# Sheet.net
KiCad netlist of a schematic drawn in Altium Designer
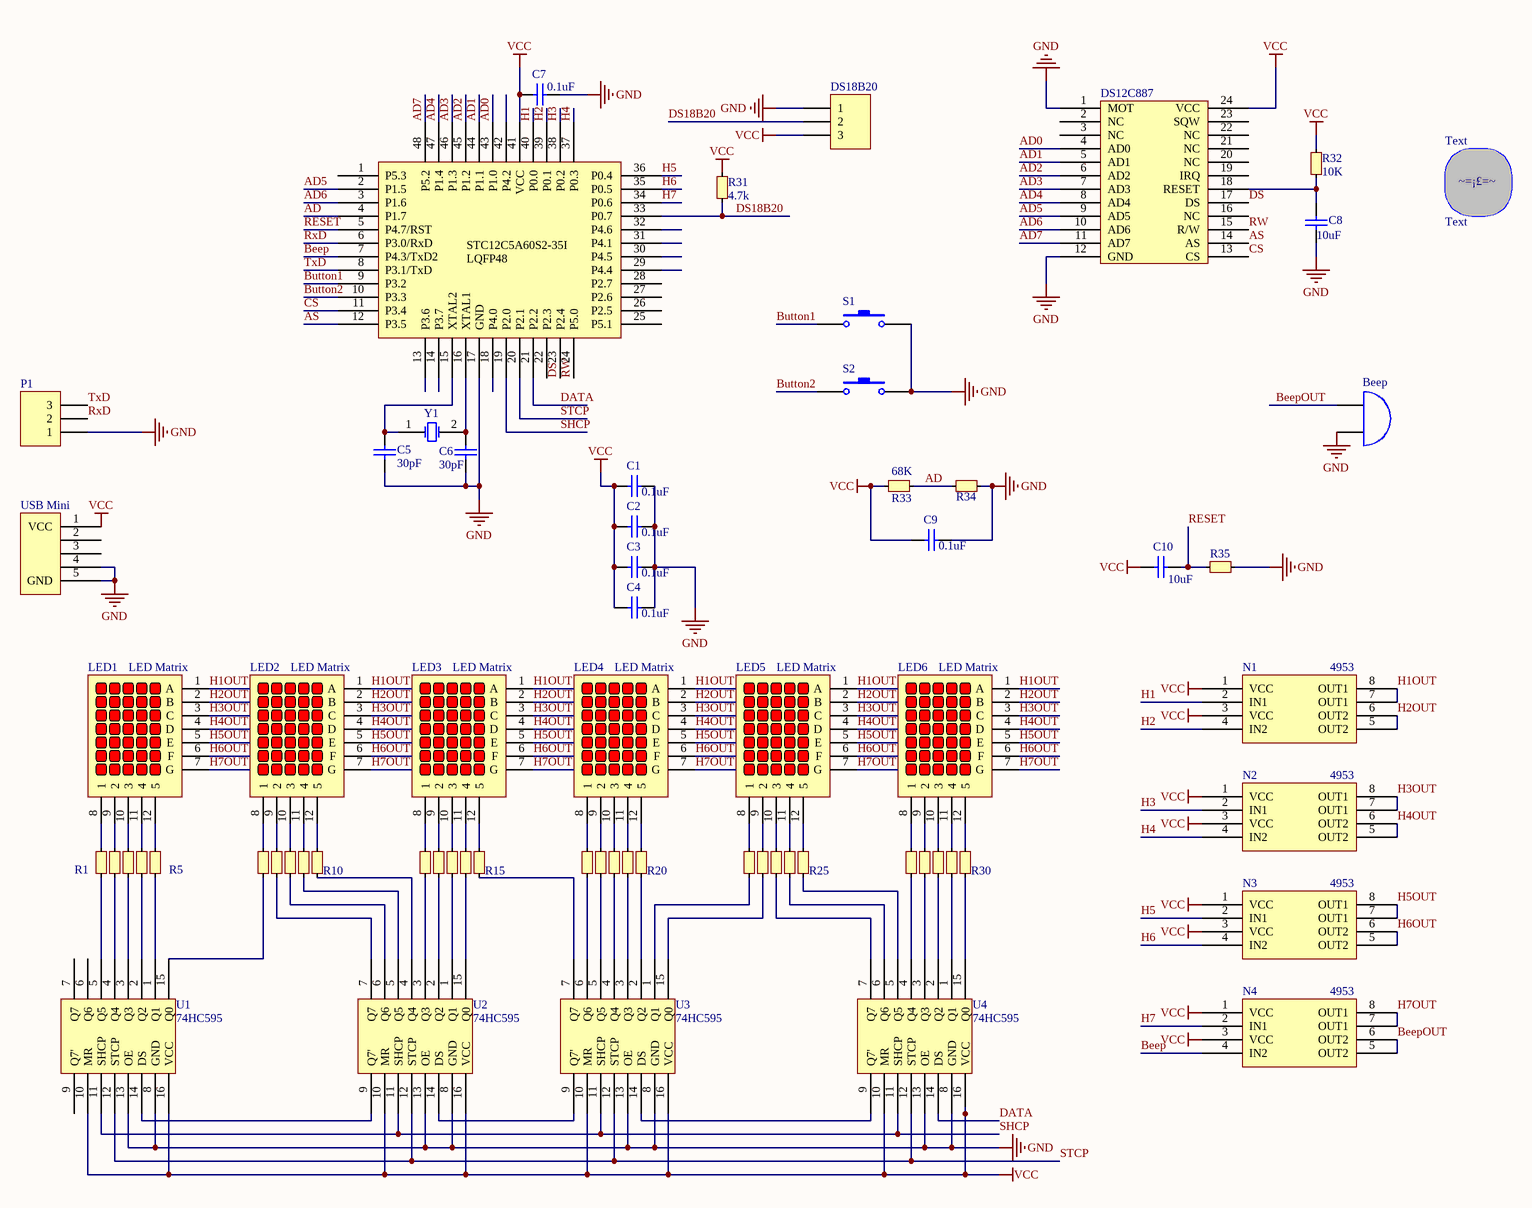
[diagram p0: Sheet.SchDoc]

(export (version "E")
  (design (tool "Eeschema 10.0.6"))
  (components
    (comp (ref "Beep")
      (value "Bell")
      (footprint "Beep")
      (description "Electrical Bell")
      (fields (field (name "PUBLISHER") "Altium Limited"))
      (libsource (lib "Miscellaneous Devices") (part "Bell"))
    )
    (comp (ref "C1")
      (value "0.1uF")
      (footprint "0805 - duplicate")
      (description "Capacitor")
      (fields (field (name "Comment") "Cap") (field (name "PUBLISHER") "Altium Limited"))
      (libsource (lib "Miscellaneous Devices") (part "Cap"))
    )
    (comp (ref "C2")
      (value "0.1uF")
      (footprint "0805 - duplicate")
      (description "Capacitor")
      (fields (field (name "Comment") "Cap") (field (name "PUBLISHER") "Altium Limited"))
      (libsource (lib "Miscellaneous Devices") (part "Cap"))
    )
    (comp (ref "C3")
      (value "0.1uF")
      (footprint "0805 - duplicate")
      (description "Capacitor")
      (fields (field (name "Comment") "Cap") (field (name "PUBLISHER") "Altium Limited"))
      (libsource (lib "Miscellaneous Devices") (part "Cap"))
    )
    (comp (ref "C4")
      (value "0.1uF")
      (footprint "0805 - duplicate")
      (description "Capacitor")
      (fields (field (name "Comment") "Cap") (field (name "PUBLISHER") "Altium Limited"))
      (libsource (lib "Miscellaneous Devices") (part "Cap"))
    )
    (comp (ref "C5")
      (value "30pF")
      (footprint "0805 - duplicate")
      (description "Capacitor")
      (fields (field (name "Comment") "Cap") (field (name "PUBLISHER") "Altium Limited"))
      (libsource (lib "Miscellaneous Devices") (part "Cap"))
    )
    (comp (ref "C6")
      (value "30pF")
      (footprint "0805 - duplicate")
      (description "Capacitor")
      (fields (field (name "Comment") "Cap") (field (name "PUBLISHER") "Altium Limited"))
      (libsource (lib "Miscellaneous Devices") (part "Cap"))
    )
    (comp (ref "C7")
      (value "0.1uF")
      (footprint "0805 - duplicate")
      (description "Capacitor")
      (fields (field (name "Comment") "Cap") (field (name "PUBLISHER") "Altium Limited"))
      (libsource (lib "Miscellaneous Devices") (part "Cap"))
    )
    (comp (ref "C8")
      (value "10uF")
      (footprint "0805 - duplicate")
      (description "Capacitor")
      (fields (field (name "Comment") "Cap") (field (name "PUBLISHER") "Altium Limited"))
      (libsource (lib "Miscellaneous Devices") (part "Cap"))
    )
    (comp (ref "C9")
      (value "0.1uF")
      (footprint "0805 - duplicate")
      (description "Capacitor")
      (fields (field (name "Comment") "Cap") (field (name "PUBLISHER") "Altium Limited"))
      (libsource (lib "Miscellaneous Devices") (part "Cap"))
    )
    (comp (ref "C10")
      (value "10uF")
      (footprint "0805 - duplicate")
      (description "Capacitor")
      (fields (field (name "Comment") "Cap") (field (name "PUBLISHER") "Altium Limited"))
      (libsource (lib "Miscellaneous Devices") (part "Cap"))
    )
    (comp (ref "DS12C887")
      (value "DS12C887")
      (footprint "Timer")
      (libsource (lib "Schlib") (part "DS12C887"))
    )
    (comp (ref "DS18B20")
      (value "Header 3")
      (footprint "TO-92")
      (description "Header, 3-Pin")
      (fields (field (name "PUBLISHER") "Altium Limited"))
      (libsource (lib "Miscellaneous Connectors") (part "Header 3"))
    )
    (comp (ref "LED1")
      (value "LED Matrix")
      (footprint "LED-Matrix 5*7")
      (fields (field (name "PUBLISHER") "Altium Limited"))
      (libsource (lib "Schlib") (part "LED-Matrix 5*7"))
    )
    (comp (ref "LED2")
      (value "LED Matrix")
      (footprint "LED-Matrix 5*7")
      (fields (field (name "PUBLISHER") "Altium Limited"))
      (libsource (lib "Schlib") (part "LED-Matrix 5*7"))
    )
    (comp (ref "LED3")
      (value "LED Matrix")
      (footprint "LED-Matrix 5*7")
      (fields (field (name "PUBLISHER") "Altium Limited"))
      (libsource (lib "Schlib") (part "LED-Matrix 5*7"))
    )
    (comp (ref "LED4")
      (value "LED Matrix")
      (footprint "LED-Matrix 5*7")
      (fields (field (name "PUBLISHER") "Altium Limited"))
      (libsource (lib "Schlib") (part "LED-Matrix 5*7"))
    )
    (comp (ref "LED5")
      (value "LED Matrix")
      (footprint "LED-Matrix 5*7")
      (fields (field (name "PUBLISHER") "Altium Limited"))
      (libsource (lib "Schlib") (part "LED-Matrix 5*7"))
    )
    (comp (ref "LED6")
      (value "LED Matrix")
      (footprint "LED-Matrix 5*7")
      (fields (field (name "PUBLISHER") "Altium Limited"))
      (libsource (lib "Schlib") (part "LED-Matrix 5*7"))
    )
    (comp (ref "MCU")
      (value "STC12C5A60S2-35I-LQFP48")
      (footprint "MCU")
      (libsource (lib "Schlib") (part "STC12C5A60S2-35I-LQFP48"))
    )
    (comp (ref "N1") (value "4953") (footprint "SO8_L") (libsource (lib "Schlib") (part "4953")))
    (comp (ref "N2") (value "4953") (footprint "SO8_L") (libsource (lib "Schlib") (part "4953")))
    (comp (ref "N3") (value "4953") (footprint "SO8_L") (libsource (lib "Schlib") (part "4953")))
    (comp (ref "N4") (value "4953") (footprint "SO8_L") (libsource (lib "Schlib") (part "4953")))
    (comp (ref "P1")
      (value "Header 3")
      (footprint "HDR1X3")
      (description "Header, 3-Pin")
      (fields (field (name "PUBLISHER") "Altium Limited"))
      (libsource (lib "") (part "Header 3_1"))
    )
    (comp (ref "R1") (value "Res") (footprint "0805") (libsource (lib "Schlib") (part "Res")))
    (comp (ref "R2") (value "Res") (footprint "0805") (libsource (lib "Schlib") (part "Res")))
    (comp (ref "R3") (value "Res") (footprint "0805") (libsource (lib "Schlib") (part "Res")))
    (comp (ref "R4") (value "Res") (footprint "0805") (libsource (lib "Schlib") (part "Res")))
    (comp (ref "R5") (value "Res") (footprint "0805") (libsource (lib "Schlib") (part "Res")))
    (comp (ref "R6") (value "Res") (footprint "0805") (libsource (lib "Schlib") (part "Res")))
    (comp (ref "R7") (value "Res") (footprint "0805") (libsource (lib "Schlib") (part "Res")))
    (comp (ref "R8") (value "Res") (footprint "0805") (libsource (lib "Schlib") (part "Res")))
    (comp (ref "R9") (value "Res") (footprint "0805") (libsource (lib "Schlib") (part "Res")))
    (comp (ref "R10") (value "Res") (footprint "0805") (libsource (lib "Schlib") (part "Res")))
    (comp (ref "R11") (value "Res") (footprint "0805") (libsource (lib "Schlib") (part "Res")))
    (comp (ref "R12") (value "Res") (footprint "0805") (libsource (lib "Schlib") (part "Res")))
    (comp (ref "R13") (value "Res") (footprint "0805") (libsource (lib "Schlib") (part "Res")))
    (comp (ref "R14") (value "Res") (footprint "0805") (libsource (lib "Schlib") (part "Res")))
    (comp (ref "R15") (value "Res") (footprint "0805") (libsource (lib "Schlib") (part "Res")))
    (comp (ref "R16") (value "Res") (footprint "0805") (libsource (lib "Schlib") (part "Res")))
    (comp (ref "R17") (value "Res") (footprint "0805") (libsource (lib "Schlib") (part "Res")))
    (comp (ref "R18") (value "Res") (footprint "0805") (libsource (lib "Schlib") (part "Res")))
    (comp (ref "R19") (value "Res") (footprint "0805") (libsource (lib "Schlib") (part "Res")))
    (comp (ref "R20") (value "Res") (footprint "0805") (libsource (lib "Schlib") (part "Res")))
    (comp (ref "R21") (value "Res") (footprint "0805") (libsource (lib "Schlib") (part "Res")))
    (comp (ref "R22") (value "Res") (footprint "0805") (libsource (lib "Schlib") (part "Res")))
    (comp (ref "R23") (value "Res") (footprint "0805") (libsource (lib "Schlib") (part "Res")))
    (comp (ref "R24") (value "Res") (footprint "0805") (libsource (lib "Schlib") (part "Res")))
    (comp (ref "R25") (value "Res") (footprint "0805") (libsource (lib "Schlib") (part "Res")))
    (comp (ref "R26") (value "Res") (footprint "0805") (libsource (lib "Schlib") (part "Res")))
    (comp (ref "R27") (value "Res") (footprint "0805") (libsource (lib "Schlib") (part "Res")))
    (comp (ref "R28") (value "Res") (footprint "0805") (libsource (lib "Schlib") (part "Res")))
    (comp (ref "R29") (value "Res") (footprint "0805") (libsource (lib "Schlib") (part "Res")))
    (comp (ref "R30") (value "Res") (footprint "0805") (libsource (lib "Schlib") (part "Res")))
    (comp (ref "R31") (value "4.7k") (footprint "0805") (libsource (lib "Schlib") (part "Res")))
    (comp (ref "R32") (value "10K") (footprint "0805") (libsource (lib "Schlib") (part "Res")))
    (comp (ref "R33") (value "68K") (footprint "0805") (libsource (lib "") (part "Res_1")))
    (comp (ref "R34") (value "Res") (footprint "R38") (libsource (lib "") (part "Res_1")))
    (comp (ref "R35") (value "Res") (footprint "0805") (libsource (lib "") (part "Res_1")))
    (comp (ref "S1")
      (value "SW-PB")
      (footprint "Button")
      (description "Switch")
      (fields (field (name "PUBLISHER") "Altium Limited"))
      (libsource (lib "Miscellaneous Devices") (part "SW-PB"))
    )
    (comp (ref "S2")
      (value "SW-PB")
      (footprint "Button")
      (description "Switch")
      (fields (field (name "PUBLISHER") "Altium Limited"))
      (libsource (lib "Miscellaneous Devices") (part "SW-PB"))
    )
    (comp (ref "Text") (value "Text") (footprint "TUSIJI_8") (libsource (lib "Schlib") (part "Text")))
    (comp (ref "U1") (value "74HC595") (footprint "SO-16_L") (libsource (lib "Schlib") (part "74HC595")))
    (comp (ref "U2") (value "74HC595") (footprint "SO-16_L") (libsource (lib "Schlib") (part "74HC595")))
    (comp (ref "U3") (value "74HC595") (footprint "SO-16_L") (libsource (lib "Schlib") (part "74HC595")))
    (comp (ref "U4") (value "74HC595") (footprint "SO-16_L") (libsource (lib "Schlib") (part "74HC595")))
    (comp (ref "USB Mini") (value "~") (footprint "Micro_USB") (libsource (lib "Schlib") (part "USB")))
    (comp (ref "Y1")
      (value "XTAL")
      (footprint "5023")
      (description "Crystal Oscillator")
      (fields (field (name "PUBLISHER") "Altium Limited"))
      (libsource (lib "Miscellaneous Devices") (part "XTAL"))
    )
  )
  (nets
    (net (code "1") (name "/AD") (class "Default")
      (node (ref "MCU") (pin "4") (pinfunction "P1.7_4") (pintype "passive"))
      (node (ref "R33") (pin "1") (pintype "passive"))
      (node (ref "R34") (pin "0") (pintype "passive"))
    )
    (net (code "2") (name "/AD0") (class "Default")
      (node (ref "DS12C887") (pin "4") (pinfunction "AD0_4") (pintype "passive"))
      (node (ref "MCU") (pin "43") (pinfunction "P1.0_43") (pintype "passive"))
    )
    (net (code "3") (name "/AD1") (class "Default")
      (node (ref "DS12C887") (pin "5") (pinfunction "AD1_5") (pintype "passive"))
      (node (ref "MCU") (pin "44") (pinfunction "P1.1_44") (pintype "passive"))
    )
    (net (code "4") (name "/AD2") (class "Default")
      (node (ref "DS12C887") (pin "6") (pinfunction "AD2_6") (pintype "passive"))
      (node (ref "MCU") (pin "45") (pinfunction "P1.2_45") (pintype "passive"))
    )
    (net (code "5") (name "/AD3") (class "Default")
      (node (ref "DS12C887") (pin "7") (pinfunction "AD3_7") (pintype "passive"))
      (node (ref "MCU") (pin "46") (pinfunction "P1.3_46") (pintype "passive"))
    )
    (net (code "6") (name "/AD4") (class "Default")
      (node (ref "DS12C887") (pin "8") (pinfunction "AD4_8") (pintype "passive"))
      (node (ref "MCU") (pin "47") (pinfunction "P1.4_47") (pintype "passive"))
    )
    (net (code "7") (name "/AD5") (class "Default")
      (node (ref "DS12C887") (pin "9") (pinfunction "AD5_9") (pintype "passive"))
      (node (ref "MCU") (pin "2") (pinfunction "P1.5_2") (pintype "passive"))
    )
    (net (code "8") (name "/AD6") (class "Default")
      (node (ref "DS12C887") (pin "10") (pinfunction "AD6_10") (pintype "passive"))
      (node (ref "MCU") (pin "3") (pinfunction "P1.6_3") (pintype "passive"))
    )
    (net (code "9") (name "/AD7") (class "Default")
      (node (ref "DS12C887") (pin "11") (pinfunction "AD7_11") (pintype "passive"))
      (node (ref "MCU") (pin "48") (pinfunction "P5.2_48") (pintype "passive"))
    )
    (net (code "10") (name "/AS") (class "Default")
      (node (ref "DS12C887") (pin "14") (pinfunction "AS_14") (pintype "passive"))
      (node (ref "MCU") (pin "12") (pinfunction "P3.5_12") (pintype "passive"))
    )
    (net (code "11") (name "/Beep") (class "Default")
      (node (ref "MCU") (pin "7") (pinfunction "P4.3/TxD2_7") (pintype "passive"))
      (node (ref "N4") (pin "4") (pinfunction "IN2_4") (pintype "passive"))
    )
    (net (code "12") (name "/BeepOUT") (class "Default")
      (node (ref "Beep") (pin "1") (pinfunction "A_1") (pintype "passive"))
      (node (ref "N4") (pin "5") (pinfunction "OUT2_5") (pintype "passive"))
      (node (ref "N4") (pin "6") (pinfunction "OUT2_6") (pintype "passive"))
    )
    (net (code "13") (name "/Button1") (class "Default")
      (node (ref "MCU") (pin "9") (pinfunction "P3.2_9") (pintype "passive"))
      (node (ref "S1") (pin "1") (pinfunction "1_1") (pintype "passive"))
    )
    (net (code "14") (name "/Button2") (class "Default")
      (node (ref "MCU") (pin "10") (pinfunction "P3.3_10") (pintype "passive"))
      (node (ref "S2") (pin "1") (pinfunction "1_1") (pintype "passive"))
    )
    (net (code "15") (name "/CS") (class "Default")
      (node (ref "DS12C887") (pin "13") (pinfunction "CS_13") (pintype "passive"))
      (node (ref "MCU") (pin "11") (pinfunction "P3.4_11") (pintype "passive"))
    )
    (net (code "16") (name "/DATA") (class "Default")
      (node (ref "MCU") (pin "21") (pinfunction "P2.2_21") (pintype "passive"))
      (node (ref "U4") (pin "14") (pinfunction "DS_14") (pintype "passive"))
    )
    (net (code "17") (name "/DS") (class "Default")
      (node (ref "DS12C887") (pin "17") (pinfunction "DS_17") (pintype "passive"))
      (node (ref "MCU") (pin "23") (pinfunction "P2.4_23") (pintype "passive"))
    )
    (net (code "18") (name "/DS18B20") (class "Default")
      (node (ref "DS18B20") (pin "2") (pinfunction "2_2") (pintype "passive"))
      (node (ref "MCU") (pin "33") (pinfunction "P0.7_33") (pintype "passive"))
      (node (ref "R31") (pin "0") (pintype "passive"))
    )
    (net (code "19") (name "/H1") (class "Default")
      (node (ref "MCU") (pin "40") (pinfunction "P0.0_40") (pintype "passive"))
      (node (ref "N1") (pin "2") (pinfunction "IN1_2") (pintype "passive"))
    )
    (net (code "20") (name "/H1OUT") (class "Default")
      (node (ref "LED1") (pin "1") (pinfunction "A_1") (pintype "passive"))
      (node (ref "LED2") (pin "1") (pinfunction "A_1") (pintype "passive"))
      (node (ref "LED3") (pin "1") (pinfunction "A_1") (pintype "passive"))
      (node (ref "LED4") (pin "1") (pinfunction "A_1") (pintype "passive"))
      (node (ref "LED5") (pin "1") (pinfunction "A_1") (pintype "passive"))
      (node (ref "LED6") (pin "1") (pinfunction "A_1") (pintype "passive"))
      (node (ref "N1") (pin "7") (pinfunction "OUT1_7") (pintype "passive"))
      (node (ref "N1") (pin "8") (pinfunction "OUT1_8") (pintype "passive"))
    )
    (net (code "21") (name "/H2") (class "Default")
      (node (ref "MCU") (pin "39") (pinfunction "P0.1_39") (pintype "passive"))
      (node (ref "N1") (pin "4") (pinfunction "IN2_4") (pintype "passive"))
    )
    (net (code "22") (name "/H2OUT") (class "Default")
      (node (ref "LED1") (pin "2") (pinfunction "B_2") (pintype "passive"))
      (node (ref "LED2") (pin "2") (pinfunction "B_2") (pintype "passive"))
      (node (ref "LED3") (pin "2") (pinfunction "B_2") (pintype "passive"))
      (node (ref "LED4") (pin "2") (pinfunction "B_2") (pintype "passive"))
      (node (ref "LED5") (pin "2") (pinfunction "B_2") (pintype "passive"))
      (node (ref "LED6") (pin "2") (pinfunction "B_2") (pintype "passive"))
      (node (ref "N1") (pin "5") (pinfunction "OUT2_5") (pintype "passive"))
      (node (ref "N1") (pin "6") (pinfunction "OUT2_6") (pintype "passive"))
    )
    (net (code "23") (name "/H3") (class "Default")
      (node (ref "MCU") (pin "38") (pinfunction "P0.2_38") (pintype "passive"))
      (node (ref "N2") (pin "2") (pinfunction "IN1_2") (pintype "passive"))
    )
    (net (code "24") (name "/H3OUT") (class "Default")
      (node (ref "LED1") (pin "3") (pinfunction "C_3") (pintype "passive"))
      (node (ref "LED2") (pin "3") (pinfunction "C_3") (pintype "passive"))
      (node (ref "LED3") (pin "3") (pinfunction "C_3") (pintype "passive"))
      (node (ref "LED4") (pin "3") (pinfunction "C_3") (pintype "passive"))
      (node (ref "LED5") (pin "3") (pinfunction "C_3") (pintype "passive"))
      (node (ref "LED6") (pin "3") (pinfunction "C_3") (pintype "passive"))
      (node (ref "N2") (pin "7") (pinfunction "OUT1_7") (pintype "passive"))
      (node (ref "N2") (pin "8") (pinfunction "OUT1_8") (pintype "passive"))
    )
    (net (code "25") (name "/H4") (class "Default")
      (node (ref "MCU") (pin "37") (pinfunction "P0.3_37") (pintype "passive"))
      (node (ref "N2") (pin "4") (pinfunction "IN2_4") (pintype "passive"))
    )
    (net (code "26") (name "/H4OUT") (class "Default")
      (node (ref "LED1") (pin "4") (pinfunction "D_4") (pintype "passive"))
      (node (ref "LED2") (pin "4") (pinfunction "D_4") (pintype "passive"))
      (node (ref "LED3") (pin "4") (pinfunction "D_4") (pintype "passive"))
      (node (ref "LED4") (pin "4") (pinfunction "D_4") (pintype "passive"))
      (node (ref "LED5") (pin "4") (pinfunction "D_4") (pintype "passive"))
      (node (ref "LED6") (pin "4") (pinfunction "D_4") (pintype "passive"))
      (node (ref "N2") (pin "5") (pinfunction "OUT2_5") (pintype "passive"))
      (node (ref "N2") (pin "6") (pinfunction "OUT2_6") (pintype "passive"))
    )
    (net (code "27") (name "/H5") (class "Default")
      (node (ref "MCU") (pin "36") (pinfunction "P0.4_36") (pintype "passive"))
      (node (ref "N3") (pin "2") (pinfunction "IN1_2") (pintype "passive"))
    )
    (net (code "28") (name "/H5OUT") (class "Default")
      (node (ref "LED1") (pin "5") (pinfunction "E_5") (pintype "passive"))
      (node (ref "LED2") (pin "5") (pinfunction "E_5") (pintype "passive"))
      (node (ref "LED3") (pin "5") (pinfunction "E_5") (pintype "passive"))
      (node (ref "LED4") (pin "5") (pinfunction "E_5") (pintype "passive"))
      (node (ref "LED5") (pin "5") (pinfunction "E_5") (pintype "passive"))
      (node (ref "LED6") (pin "5") (pinfunction "E_5") (pintype "passive"))
      (node (ref "N3") (pin "7") (pinfunction "OUT1_7") (pintype "passive"))
      (node (ref "N3") (pin "8") (pinfunction "OUT1_8") (pintype "passive"))
    )
    (net (code "29") (name "/H6") (class "Default")
      (node (ref "MCU") (pin "35") (pinfunction "P0.5_35") (pintype "passive"))
      (node (ref "N3") (pin "4") (pinfunction "IN2_4") (pintype "passive"))
    )
    (net (code "30") (name "/H6OUT") (class "Default")
      (node (ref "LED1") (pin "6") (pinfunction "F_6") (pintype "passive"))
      (node (ref "LED2") (pin "6") (pinfunction "F_6") (pintype "passive"))
      (node (ref "LED3") (pin "6") (pinfunction "F_6") (pintype "passive"))
      (node (ref "LED4") (pin "6") (pinfunction "F_6") (pintype "passive"))
      (node (ref "LED5") (pin "6") (pinfunction "F_6") (pintype "passive"))
      (node (ref "LED6") (pin "6") (pinfunction "F_6") (pintype "passive"))
      (node (ref "N3") (pin "5") (pinfunction "OUT2_5") (pintype "passive"))
      (node (ref "N3") (pin "6") (pinfunction "OUT2_6") (pintype "passive"))
    )
    (net (code "31") (name "/H7") (class "Default")
      (node (ref "MCU") (pin "34") (pinfunction "P0.6_34") (pintype "passive"))
      (node (ref "N4") (pin "2") (pinfunction "IN1_2") (pintype "passive"))
    )
    (net (code "32") (name "/H7OUT") (class "Default")
      (node (ref "LED1") (pin "7") (pinfunction "G_7") (pintype "passive"))
      (node (ref "LED2") (pin "7") (pinfunction "G_7") (pintype "passive"))
      (node (ref "LED3") (pin "7") (pinfunction "G_7") (pintype "passive"))
      (node (ref "LED4") (pin "7") (pinfunction "G_7") (pintype "passive"))
      (node (ref "LED5") (pin "7") (pinfunction "G_7") (pintype "passive"))
      (node (ref "LED6") (pin "7") (pinfunction "G_7") (pintype "passive"))
      (node (ref "N4") (pin "7") (pinfunction "OUT1_7") (pintype "passive"))
      (node (ref "N4") (pin "8") (pinfunction "OUT1_8") (pintype "passive"))
    )
    (net (code "33") (name "/RESET") (class "Default")
      (node (ref "C10") (pin "2") (pinfunction "2_2") (pintype "passive"))
      (node (ref "MCU") (pin "5") (pinfunction "P4.7/RST_5") (pintype "passive"))
      (node (ref "R35") (pin "0") (pintype "passive"))
    )
    (net (code "34") (name "/RW") (class "Default")
      (node (ref "DS12C887") (pin "15") (pinfunction "R/W_15") (pintype "passive"))
      (node (ref "MCU") (pin "24") (pinfunction "P5.0_24") (pintype "passive"))
    )
    (net (code "35") (name "/RxD") (class "Default")
      (node (ref "MCU") (pin "6") (pinfunction "P3.0/RxD_6") (pintype "passive"))
      (node (ref "P1") (pin "2") (pinfunction "2_2") (pintype "passive"))
    )
    (net (code "36") (name "/SHCP") (class "Default")
      (node (ref "MCU") (pin "19") (pinfunction "P2.0_19") (pintype "passive"))
      (node (ref "U1") (pin "11") (pinfunction "SHCP_11") (pintype "passive"))
      (node (ref "U2") (pin "11") (pinfunction "SHCP_11") (pintype "passive"))
      (node (ref "U3") (pin "11") (pinfunction "SHCP_11") (pintype "passive"))
      (node (ref "U4") (pin "11") (pinfunction "SHCP_11") (pintype "passive"))
    )
    (net (code "37") (name "/STCP") (class "Default")
      (node (ref "MCU") (pin "20") (pinfunction "P2.1_20") (pintype "passive"))
      (node (ref "U1") (pin "12") (pinfunction "STCP_12") (pintype "passive"))
      (node (ref "U2") (pin "12") (pinfunction "STCP_12") (pintype "passive"))
      (node (ref "U3") (pin "12") (pinfunction "STCP_12") (pintype "passive"))
      (node (ref "U4") (pin "12") (pinfunction "STCP_12") (pintype "passive"))
    )
    (net (code "38") (name "/TxD") (class "Default")
      (node (ref "MCU") (pin "8") (pinfunction "P3.1/TxD_8") (pintype "passive"))
      (node (ref "P1") (pin "3") (pinfunction "3_3") (pintype "passive"))
    )
    (net (code "39") (name "GND") (class "Default")
      (node (ref "Beep") (pin "2") (pinfunction "B_2") (pintype "passive"))
      (node (ref "C1") (pin "2") (pinfunction "2_2") (pintype "passive"))
      (node (ref "C2") (pin "2") (pinfunction "2_2") (pintype "passive"))
      (node (ref "C3") (pin "2") (pinfunction "2_2") (pintype "passive"))
      (node (ref "C4") (pin "2") (pinfunction "2_2") (pintype "passive"))
      (node (ref "C5") (pin "1") (pinfunction "1_1") (pintype "passive"))
      (node (ref "C6") (pin "1") (pinfunction "1_1") (pintype "passive"))
      (node (ref "C7") (pin "2") (pinfunction "2_2") (pintype "passive"))
      (node (ref "C8") (pin "1") (pinfunction "1_1") (pintype "passive"))
      (node (ref "C9") (pin "2") (pinfunction "2_2") (pintype "passive"))
      (node (ref "DS12C887") (pin "1") (pinfunction "MOT_1") (pintype "passive"))
      (node (ref "DS12C887") (pin "12") (pinfunction "GND_12") (pintype "passive"))
      (node (ref "DS18B20") (pin "1") (pinfunction "1_1") (pintype "passive"))
      (node (ref "MCU") (pin "17") (pinfunction "GND_17") (pintype "passive"))
      (node (ref "P1") (pin "1") (pinfunction "1_1") (pintype "passive"))
      (node (ref "R34") (pin "1") (pintype "passive"))
      (node (ref "R35") (pin "1") (pintype "passive"))
      (node (ref "S1") (pin "2") (pinfunction "2_2") (pintype "passive"))
      (node (ref "S2") (pin "2") (pinfunction "2_2") (pintype "passive"))
      (node (ref "U1") (pin "13") (pinfunction "OE_13") (pintype "passive"))
      (node (ref "U1") (pin "8") (pinfunction "GND_8") (pintype "passive"))
      (node (ref "U2") (pin "13") (pinfunction "OE_13") (pintype "passive"))
      (node (ref "U2") (pin "8") (pinfunction "GND_8") (pintype "passive"))
      (node (ref "U3") (pin "13") (pinfunction "OE_13") (pintype "passive"))
      (node (ref "U3") (pin "8") (pinfunction "GND_8") (pintype "passive"))
      (node (ref "U4") (pin "13") (pinfunction "OE_13") (pintype "passive"))
      (node (ref "U4") (pin "8") (pinfunction "GND_8") (pintype "passive"))
      (node (ref "USB Mini") (pin "4") (pinfunction "4_4") (pintype "passive"))
      (node (ref "USB Mini") (pin "5") (pinfunction "GND_5") (pintype "passive"))
    )
    (net (code "40") (name "Net-(DS12C887-RESET)") (class "Default")
      (node (ref "C8") (pin "2") (pinfunction "2_2") (pintype "passive"))
      (node (ref "DS12C887") (pin "18") (pinfunction "RESET_18") (pintype "passive"))
      (node (ref "R32") (pin "0") (pintype "passive"))
    )
    (net (code "41") (name "Net-(LED1-1)") (class "Default")
      (node (ref "LED1") (pin "8") (pinfunction "1_8") (pintype "passive"))
      (node (ref "R1") (pin "1") (pintype "passive"))
    )
    (net (code "42") (name "Net-(LED1-2)") (class "Default")
      (node (ref "LED1") (pin "9") (pinfunction "2_9") (pintype "passive"))
      (node (ref "R2") (pin "1") (pintype "passive"))
    )
    (net (code "43") (name "Net-(LED1-3)") (class "Default")
      (node (ref "LED1") (pin "10") (pinfunction "3_10") (pintype "passive"))
      (node (ref "R3") (pin "1") (pintype "passive"))
    )
    (net (code "44") (name "Net-(LED1-4)") (class "Default")
      (node (ref "LED1") (pin "11") (pinfunction "4_11") (pintype "passive"))
      (node (ref "R4") (pin "1") (pintype "passive"))
    )
    (net (code "45") (name "Net-(LED1-5)") (class "Default")
      (node (ref "LED1") (pin "12") (pinfunction "5_12") (pintype "passive"))
      (node (ref "R5") (pin "1") (pintype "passive"))
    )
    (net (code "46") (name "Net-(LED2-1)") (class "Default")
      (node (ref "LED2") (pin "8") (pinfunction "1_8") (pintype "passive"))
      (node (ref "R6") (pin "1") (pintype "passive"))
    )
    (net (code "47") (name "Net-(LED2-2)") (class "Default")
      (node (ref "LED2") (pin "9") (pinfunction "2_9") (pintype "passive"))
      (node (ref "R7") (pin "1") (pintype "passive"))
    )
    (net (code "48") (name "Net-(LED2-3)") (class "Default")
      (node (ref "LED2") (pin "10") (pinfunction "3_10") (pintype "passive"))
      (node (ref "R8") (pin "1") (pintype "passive"))
    )
    (net (code "49") (name "Net-(LED2-4)") (class "Default")
      (node (ref "LED2") (pin "11") (pinfunction "4_11") (pintype "passive"))
      (node (ref "R9") (pin "1") (pintype "passive"))
    )
    (net (code "50") (name "Net-(LED2-5)") (class "Default")
      (node (ref "LED2") (pin "12") (pinfunction "5_12") (pintype "passive"))
      (node (ref "R10") (pin "1") (pintype "passive"))
    )
    (net (code "51") (name "Net-(LED3-1)") (class "Default")
      (node (ref "LED3") (pin "8") (pinfunction "1_8") (pintype "passive"))
      (node (ref "R11") (pin "1") (pintype "passive"))
    )
    (net (code "52") (name "Net-(LED3-2)") (class "Default")
      (node (ref "LED3") (pin "9") (pinfunction "2_9") (pintype "passive"))
      (node (ref "R12") (pin "1") (pintype "passive"))
    )
    (net (code "53") (name "Net-(LED3-3)") (class "Default")
      (node (ref "LED3") (pin "10") (pinfunction "3_10") (pintype "passive"))
      (node (ref "R13") (pin "1") (pintype "passive"))
    )
    (net (code "54") (name "Net-(LED3-4)") (class "Default")
      (node (ref "LED3") (pin "11") (pinfunction "4_11") (pintype "passive"))
      (node (ref "R14") (pin "1") (pintype "passive"))
    )
    (net (code "55") (name "Net-(LED3-5)") (class "Default")
      (node (ref "LED3") (pin "12") (pinfunction "5_12") (pintype "passive"))
      (node (ref "R15") (pin "1") (pintype "passive"))
    )
    (net (code "56") (name "Net-(LED4-1)") (class "Default")
      (node (ref "LED4") (pin "8") (pinfunction "1_8") (pintype "passive"))
      (node (ref "R16") (pin "1") (pintype "passive"))
    )
    (net (code "57") (name "Net-(LED4-2)") (class "Default")
      (node (ref "LED4") (pin "9") (pinfunction "2_9") (pintype "passive"))
      (node (ref "R17") (pin "1") (pintype "passive"))
    )
    (net (code "58") (name "Net-(LED4-3)") (class "Default")
      (node (ref "LED4") (pin "10") (pinfunction "3_10") (pintype "passive"))
      (node (ref "R18") (pin "1") (pintype "passive"))
    )
    (net (code "59") (name "Net-(LED4-4)") (class "Default")
      (node (ref "LED4") (pin "11") (pinfunction "4_11") (pintype "passive"))
      (node (ref "R19") (pin "1") (pintype "passive"))
    )
    (net (code "60") (name "Net-(LED4-5)") (class "Default")
      (node (ref "LED4") (pin "12") (pinfunction "5_12") (pintype "passive"))
      (node (ref "R20") (pin "1") (pintype "passive"))
    )
    (net (code "61") (name "Net-(LED5-1)") (class "Default")
      (node (ref "LED5") (pin "8") (pinfunction "1_8") (pintype "passive"))
      (node (ref "R21") (pin "1") (pintype "passive"))
    )
    (net (code "62") (name "Net-(LED5-2)") (class "Default")
      (node (ref "LED5") (pin "9") (pinfunction "2_9") (pintype "passive"))
      (node (ref "R22") (pin "1") (pintype "passive"))
    )
    (net (code "63") (name "Net-(LED5-3)") (class "Default")
      (node (ref "LED5") (pin "10") (pinfunction "3_10") (pintype "passive"))
      (node (ref "R23") (pin "1") (pintype "passive"))
    )
    (net (code "64") (name "Net-(LED5-4)") (class "Default")
      (node (ref "LED5") (pin "11") (pinfunction "4_11") (pintype "passive"))
      (node (ref "R24") (pin "1") (pintype "passive"))
    )
    (net (code "65") (name "Net-(LED5-5)") (class "Default")
      (node (ref "LED5") (pin "12") (pinfunction "5_12") (pintype "passive"))
      (node (ref "R25") (pin "1") (pintype "passive"))
    )
    (net (code "66") (name "Net-(LED6-1)") (class "Default")
      (node (ref "LED6") (pin "8") (pinfunction "1_8") (pintype "passive"))
      (node (ref "R26") (pin "1") (pintype "passive"))
    )
    (net (code "67") (name "Net-(LED6-2)") (class "Default")
      (node (ref "LED6") (pin "9") (pinfunction "2_9") (pintype "passive"))
      (node (ref "R27") (pin "1") (pintype "passive"))
    )
    (net (code "68") (name "Net-(LED6-3)") (class "Default")
      (node (ref "LED6") (pin "10") (pinfunction "3_10") (pintype "passive"))
      (node (ref "R28") (pin "1") (pintype "passive"))
    )
    (net (code "69") (name "Net-(LED6-4)") (class "Default")
      (node (ref "LED6") (pin "11") (pinfunction "4_11") (pintype "passive"))
      (node (ref "R29") (pin "1") (pintype "passive"))
    )
    (net (code "70") (name "Net-(LED6-5)") (class "Default")
      (node (ref "LED6") (pin "12") (pinfunction "5_12") (pintype "passive"))
      (node (ref "R30") (pin "1") (pintype "passive"))
    )
    (net (code "71") (name "Net-(MCU-XTAL1)") (class "Default")
      (node (ref "C6") (pin "2") (pinfunction "2_2") (pintype "passive"))
      (node (ref "MCU") (pin "16") (pinfunction "XTAL1_16") (pintype "passive"))
      (node (ref "Y1") (pin "2") (pinfunction "OSC2_2") (pintype "passive"))
    )
    (net (code "72") (name "Net-(MCU-XTAL2)") (class "Default")
      (node (ref "C5") (pin "2") (pinfunction "2_2") (pintype "passive"))
      (node (ref "MCU") (pin "15") (pinfunction "XTAL2_15") (pintype "passive"))
      (node (ref "Y1") (pin "1") (pinfunction "OSC1_1") (pintype "passive"))
    )
    (net (code "73") (name "Net-(U1-DS)") (class "Default")
      (node (ref "U1") (pin "14") (pinfunction "DS_14") (pintype "passive"))
      (node (ref "U2") (pin "9") (pinfunction "Q7'_9") (pintype "passive"))
    )
    (net (code "74") (name "Net-(U1-Q0)") (class "Default")
      (node (ref "R6") (pin "0") (pintype "passive"))
      (node (ref "U1") (pin "15") (pinfunction "Q0_15") (pintype "passive"))
    )
    (net (code "75") (name "Net-(U1-Q1)") (class "Default")
      (node (ref "R5") (pin "0") (pintype "passive"))
      (node (ref "U1") (pin "1") (pinfunction "Q1_1") (pintype "passive"))
    )
    (net (code "76") (name "Net-(U1-Q2)") (class "Default")
      (node (ref "R4") (pin "0") (pintype "passive"))
      (node (ref "U1") (pin "2") (pinfunction "Q2_2") (pintype "passive"))
    )
    (net (code "77") (name "Net-(U1-Q3)") (class "Default")
      (node (ref "R3") (pin "0") (pintype "passive"))
      (node (ref "U1") (pin "3") (pinfunction "Q3_3") (pintype "passive"))
    )
    (net (code "78") (name "Net-(U1-Q4)") (class "Default")
      (node (ref "R2") (pin "0") (pintype "passive"))
      (node (ref "U1") (pin "4") (pinfunction "Q4_4") (pintype "passive"))
    )
    (net (code "79") (name "Net-(U1-Q5)") (class "Default")
      (node (ref "R1") (pin "0") (pintype "passive"))
      (node (ref "U1") (pin "5") (pinfunction "Q5_5") (pintype "passive"))
    )
    (net (code "80") (name "Net-(U2-DS)") (class "Default")
      (node (ref "U2") (pin "14") (pinfunction "DS_14") (pintype "passive"))
      (node (ref "U3") (pin "9") (pinfunction "Q7'_9") (pintype "passive"))
    )
    (net (code "81") (name "Net-(U2-Q0)") (class "Default")
      (node (ref "R14") (pin "0") (pintype "passive"))
      (node (ref "U2") (pin "15") (pinfunction "Q0_15") (pintype "passive"))
    )
    (net (code "82") (name "Net-(U2-Q1)") (class "Default")
      (node (ref "R13") (pin "0") (pintype "passive"))
      (node (ref "U2") (pin "1") (pinfunction "Q1_1") (pintype "passive"))
    )
    (net (code "83") (name "Net-(U2-Q2)") (class "Default")
      (node (ref "R12") (pin "0") (pintype "passive"))
      (node (ref "U2") (pin "2") (pinfunction "Q2_2") (pintype "passive"))
    )
    (net (code "84") (name "Net-(U2-Q3)") (class "Default")
      (node (ref "R11") (pin "0") (pintype "passive"))
      (node (ref "U2") (pin "3") (pinfunction "Q3_3") (pintype "passive"))
    )
    (net (code "85") (name "Net-(U2-Q4)") (class "Default")
      (node (ref "R10") (pin "0") (pintype "passive"))
      (node (ref "U2") (pin "4") (pinfunction "Q4_4") (pintype "passive"))
    )
    (net (code "86") (name "Net-(U2-Q5)") (class "Default")
      (node (ref "R9") (pin "0") (pintype "passive"))
      (node (ref "U2") (pin "5") (pinfunction "Q5_5") (pintype "passive"))
    )
    (net (code "87") (name "Net-(U2-Q6)") (class "Default")
      (node (ref "R8") (pin "0") (pintype "passive"))
      (node (ref "U2") (pin "6") (pinfunction "Q6_6") (pintype "passive"))
    )
    (net (code "88") (name "Net-(U2-Q7)") (class "Default")
      (node (ref "R7") (pin "0") (pintype "passive"))
      (node (ref "U2") (pin "7") (pinfunction "Q7_7") (pintype "passive"))
    )
    (net (code "89") (name "Net-(U3-DS)") (class "Default")
      (node (ref "U3") (pin "14") (pinfunction "DS_14") (pintype "passive"))
      (node (ref "U4") (pin "9") (pinfunction "Q7'_9") (pintype "passive"))
    )
    (net (code "90") (name "Net-(U3-Q0)") (class "Default")
      (node (ref "R22") (pin "0") (pintype "passive"))
      (node (ref "U3") (pin "15") (pinfunction "Q0_15") (pintype "passive"))
    )
    (net (code "91") (name "Net-(U3-Q1)") (class "Default")
      (node (ref "R21") (pin "0") (pintype "passive"))
      (node (ref "U3") (pin "1") (pinfunction "Q1_1") (pintype "passive"))
    )
    (net (code "92") (name "Net-(U3-Q2)") (class "Default")
      (node (ref "R20") (pin "0") (pintype "passive"))
      (node (ref "U3") (pin "2") (pinfunction "Q2_2") (pintype "passive"))
    )
    (net (code "93") (name "Net-(U3-Q3)") (class "Default")
      (node (ref "R19") (pin "0") (pintype "passive"))
      (node (ref "U3") (pin "3") (pinfunction "Q3_3") (pintype "passive"))
    )
    (net (code "94") (name "Net-(U3-Q4)") (class "Default")
      (node (ref "R18") (pin "0") (pintype "passive"))
      (node (ref "U3") (pin "4") (pinfunction "Q4_4") (pintype "passive"))
    )
    (net (code "95") (name "Net-(U3-Q5)") (class "Default")
      (node (ref "R17") (pin "0") (pintype "passive"))
      (node (ref "U3") (pin "5") (pinfunction "Q5_5") (pintype "passive"))
    )
    (net (code "96") (name "Net-(U3-Q6)") (class "Default")
      (node (ref "R16") (pin "0") (pintype "passive"))
      (node (ref "U3") (pin "6") (pinfunction "Q6_6") (pintype "passive"))
    )
    (net (code "97") (name "Net-(U3-Q7)") (class "Default")
      (node (ref "R15") (pin "0") (pintype "passive"))
      (node (ref "U3") (pin "7") (pinfunction "Q7_7") (pintype "passive"))
    )
    (net (code "98") (name "Net-(U4-Q0)") (class "Default")
      (node (ref "R30") (pin "0") (pintype "passive"))
      (node (ref "U4") (pin "15") (pinfunction "Q0_15") (pintype "passive"))
    )
    (net (code "99") (name "Net-(U4-Q1)") (class "Default")
      (node (ref "R29") (pin "0") (pintype "passive"))
      (node (ref "U4") (pin "1") (pinfunction "Q1_1") (pintype "passive"))
    )
    (net (code "100") (name "Net-(U4-Q2)") (class "Default")
      (node (ref "R28") (pin "0") (pintype "passive"))
      (node (ref "U4") (pin "2") (pinfunction "Q2_2") (pintype "passive"))
    )
    (net (code "101") (name "Net-(U4-Q3)") (class "Default")
      (node (ref "R27") (pin "0") (pintype "passive"))
      (node (ref "U4") (pin "3") (pinfunction "Q3_3") (pintype "passive"))
    )
    (net (code "102") (name "Net-(U4-Q4)") (class "Default")
      (node (ref "R26") (pin "0") (pintype "passive"))
      (node (ref "U4") (pin "4") (pinfunction "Q4_4") (pintype "passive"))
    )
    (net (code "103") (name "Net-(U4-Q5)") (class "Default")
      (node (ref "R25") (pin "0") (pintype "passive"))
      (node (ref "U4") (pin "5") (pinfunction "Q5_5") (pintype "passive"))
    )
    (net (code "104") (name "Net-(U4-Q6)") (class "Default")
      (node (ref "R24") (pin "0") (pintype "passive"))
      (node (ref "U4") (pin "6") (pinfunction "Q6_6") (pintype "passive"))
    )
    (net (code "105") (name "Net-(U4-Q7)") (class "Default")
      (node (ref "R23") (pin "0") (pintype "passive"))
      (node (ref "U4") (pin "7") (pinfunction "Q7_7") (pintype "passive"))
    )
    (net (code "106") (name "VCC") (class "Default")
      (node (ref "C1") (pin "1") (pinfunction "1_1") (pintype "passive"))
      (node (ref "C10") (pin "1") (pinfunction "1_1") (pintype "passive"))
      (node (ref "C2") (pin "1") (pinfunction "1_1") (pintype "passive"))
      (node (ref "C3") (pin "1") (pinfunction "1_1") (pintype "passive"))
      (node (ref "C4") (pin "1") (pinfunction "1_1") (pintype "passive"))
      (node (ref "C7") (pin "1") (pinfunction "1_1") (pintype "passive"))
      (node (ref "C9") (pin "1") (pinfunction "1_1") (pintype "passive"))
      (node (ref "DS12C887") (pin "24") (pinfunction "VCC_24") (pintype "passive"))
      (node (ref "DS18B20") (pin "3") (pinfunction "3_3") (pintype "passive"))
      (node (ref "MCU") (pin "41") (pinfunction "VCC_41") (pintype "passive"))
      (node (ref "N1") (pin "1") (pinfunction "VCC_1") (pintype "passive"))
      (node (ref "N1") (pin "3") (pinfunction "VCC_3") (pintype "passive"))
      (node (ref "N2") (pin "1") (pinfunction "VCC_1") (pintype "passive"))
      (node (ref "N2") (pin "3") (pinfunction "VCC_3") (pintype "passive"))
      (node (ref "N3") (pin "1") (pinfunction "VCC_1") (pintype "passive"))
      (node (ref "N3") (pin "3") (pinfunction "VCC_3") (pintype "passive"))
      (node (ref "N4") (pin "1") (pinfunction "VCC_1") (pintype "passive"))
      (node (ref "N4") (pin "3") (pinfunction "VCC_3") (pintype "passive"))
      (node (ref "R31") (pin "1") (pintype "passive"))
      (node (ref "R32") (pin "1") (pintype "passive"))
      (node (ref "R33") (pin "0") (pintype "passive"))
      (node (ref "U1") (pin "10") (pinfunction "MR_10") (pintype "passive"))
      (node (ref "U1") (pin "16") (pinfunction "VCC_16") (pintype "passive"))
      (node (ref "U2") (pin "10") (pinfunction "MR_10") (pintype "passive"))
      (node (ref "U2") (pin "16") (pinfunction "VCC_16") (pintype "passive"))
      (node (ref "U3") (pin "10") (pinfunction "MR_10") (pintype "passive"))
      (node (ref "U3") (pin "16") (pinfunction "VCC_16") (pintype "passive"))
      (node (ref "U4") (pin "10") (pinfunction "MR_10") (pintype "passive"))
      (node (ref "U4") (pin "16") (pinfunction "VCC_16") (pintype "passive"))
      (node (ref "USB Mini") (pin "1") (pinfunction "VCC_1") (pintype "passive"))
    )
    (net (code "107") (name "unconnected-(DS12C887-IRQ-Pad19)") (class "Default")
      (node (ref "DS12C887") (pin "19") (pinfunction "IRQ_19") (pintype "passive"))
    )
    (net (code "108") (name "unconnected-(DS12C887-NC-Pad2)") (class "Default")
      (node (ref "DS12C887") (pin "2") (pinfunction "NC_2") (pintype "passive"))
    )
    (net (code "109") (name "unconnected-(DS12C887-NC-Pad3)") (class "Default")
      (node (ref "DS12C887") (pin "3") (pinfunction "NC_3") (pintype "passive"))
    )
    (net (code "110") (name "unconnected-(DS12C887-NC-Pad16)") (class "Default")
      (node (ref "DS12C887") (pin "16") (pinfunction "NC_16") (pintype "passive"))
    )
    (net (code "111") (name "unconnected-(DS12C887-NC-Pad20)") (class "Default")
      (node (ref "DS12C887") (pin "20") (pinfunction "NC_20") (pintype "passive"))
    )
    (net (code "112") (name "unconnected-(DS12C887-NC-Pad21)") (class "Default")
      (node (ref "DS12C887") (pin "21") (pinfunction "NC_21") (pintype "passive"))
    )
    (net (code "113") (name "unconnected-(DS12C887-NC-Pad22)") (class "Default")
      (node (ref "DS12C887") (pin "22") (pinfunction "NC_22") (pintype "passive"))
    )
    (net (code "114") (name "unconnected-(DS12C887-SQW-Pad23)") (class "Default")
      (node (ref "DS12C887") (pin "23") (pinfunction "SQW_23") (pintype "passive"))
    )
    (net (code "115") (name "unconnected-(MCU-P2.3-Pad22)") (class "Default")
      (node (ref "MCU") (pin "22") (pinfunction "P2.3_22") (pintype "passive"))
    )
    (net (code "116") (name "unconnected-(MCU-P2.5-Pad26)") (class "Default")
      (node (ref "MCU") (pin "26") (pinfunction "P2.5_26") (pintype "passive"))
    )
    (net (code "117") (name "unconnected-(MCU-P2.6-Pad27)") (class "Default")
      (node (ref "MCU") (pin "27") (pinfunction "P2.6_27") (pintype "passive"))
    )
    (net (code "118") (name "unconnected-(MCU-P2.7-Pad28)") (class "Default")
      (node (ref "MCU") (pin "28") (pinfunction "P2.7_28") (pintype "passive"))
    )
    (net (code "119") (name "unconnected-(MCU-P3.6-Pad13)") (class "Default")
      (node (ref "MCU") (pin "13") (pinfunction "P3.6_13") (pintype "passive"))
    )
    (net (code "120") (name "unconnected-(MCU-P3.7-Pad14)") (class "Default")
      (node (ref "MCU") (pin "14") (pinfunction "P3.7_14") (pintype "passive"))
    )
    (net (code "121") (name "unconnected-(MCU-P4.0-Pad18)") (class "Default")
      (node (ref "MCU") (pin "18") (pinfunction "P4.0_18") (pintype "passive"))
    )
    (net (code "122") (name "unconnected-(MCU-P4.1-Pad31)") (class "Default")
      (node (ref "MCU") (pin "31") (pinfunction "P4.1_31") (pintype "passive"))
    )
    (net (code "123") (name "unconnected-(MCU-P4.2-Pad42)") (class "Default")
      (node (ref "MCU") (pin "42") (pinfunction "P4.2_42") (pintype "passive"))
    )
    (net (code "124") (name "unconnected-(MCU-P4.4-Pad29)") (class "Default")
      (node (ref "MCU") (pin "29") (pinfunction "P4.4_29") (pintype "passive"))
    )
    (net (code "125") (name "unconnected-(MCU-P4.5-Pad30)") (class "Default")
      (node (ref "MCU") (pin "30") (pinfunction "P4.5_30") (pintype "passive"))
    )
    (net (code "126") (name "unconnected-(MCU-P4.6-Pad32)") (class "Default")
      (node (ref "MCU") (pin "32") (pinfunction "P4.6_32") (pintype "passive"))
    )
    (net (code "127") (name "unconnected-(MCU-P5.1-Pad25)") (class "Default")
      (node (ref "MCU") (pin "25") (pinfunction "P5.1_25") (pintype "passive"))
    )
    (net (code "128") (name "unconnected-(MCU-P5.3-Pad1)") (class "Default")
      (node (ref "MCU") (pin "1") (pinfunction "P5.3_1") (pintype "passive"))
    )
    (net (code "129") (name "unconnected-(U1-Q6-Pad6)") (class "Default")
      (node (ref "U1") (pin "6") (pinfunction "Q6_6") (pintype "passive"))
    )
    (net (code "130") (name "unconnected-(U1-Q7'-Pad9)") (class "Default")
      (node (ref "U1") (pin "9") (pinfunction "Q7'_9") (pintype "passive"))
    )
    (net (code "131") (name "unconnected-(U1-Q7-Pad7)") (class "Default")
      (node (ref "U1") (pin "7") (pinfunction "Q7_7") (pintype "passive"))
    )
    (net (code "132") (name "unconnected-(USB Mini-Pad2)") (class "Default")
      (node (ref "USB Mini") (pin "2") (pinfunction "2_2") (pintype "passive"))
    )
    (net (code "133") (name "unconnected-(USB Mini-Pad3)") (class "Default")
      (node (ref "USB Mini") (pin "3") (pinfunction "3_3") (pintype "passive"))
    )
  )
)
